# Slot_Pullups_and_Pulldowns.net
KiCad netlist of a schematic drawn in Altium Designer
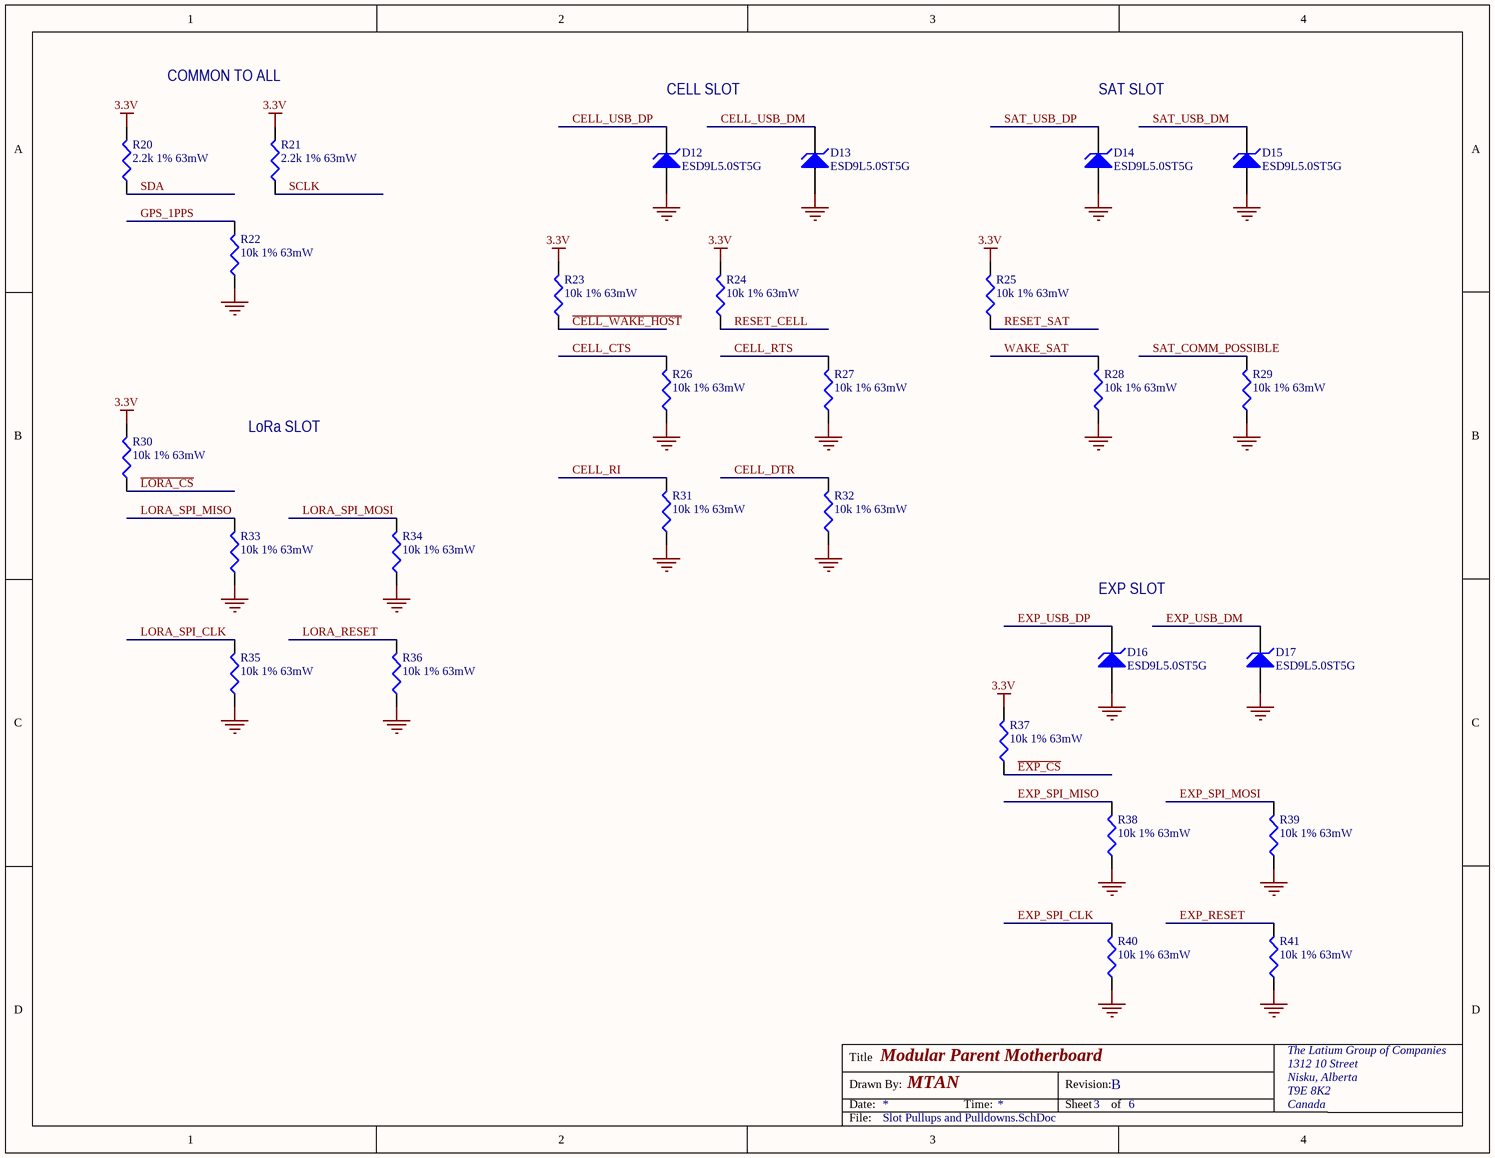
[diagram p0: Slot Pullups and Pulldowns.SchDoc]

(export (version "E")
  (design (tool "Eeschema 10.0.6"))
  (components
    (comp (ref "D12")
      (value "ESD9L5.0ST5G")
      (footprint "SOD-923")
      (description "TVS DIODE 5V 9.8V SOD923")
      (fields (field (name "MANUFACTURER") "ON Semiconductor"))
      (libsource (lib "Miscellaneous Devices") (part "D Zener"))
    )
    (comp (ref "D13")
      (value "ESD9L5.0ST5G")
      (footprint "SOD-923")
      (description "TVS DIODE 5V 9.8V SOD923")
      (fields (field (name "MANUFACTURER") "ON Semiconductor"))
      (libsource (lib "Miscellaneous Devices") (part "D Zener"))
    )
    (comp (ref "D14")
      (value "ESD9L5.0ST5G")
      (footprint "SOD-923")
      (description "TVS DIODE 5V 9.8V SOD923")
      (fields (field (name "MANUFACTURER") "ON Semiconductor"))
      (libsource (lib "Miscellaneous Devices") (part "D Zener"))
    )
    (comp (ref "D15")
      (value "ESD9L5.0ST5G")
      (footprint "SOD-923")
      (description "TVS DIODE 5V 9.8V SOD923")
      (fields (field (name "MANUFACTURER") "ON Semiconductor"))
      (libsource (lib "Miscellaneous Devices") (part "D Zener"))
    )
    (comp (ref "D16")
      (value "ESD9L5.0ST5G")
      (footprint "SOD-923")
      (description "TVS DIODE 5V 9.8V SOD923")
      (fields (field (name "MANUFACTURER") "ON Semiconductor"))
      (libsource (lib "Miscellaneous Devices") (part "D Zener"))
    )
    (comp (ref "D17")
      (value "ESD9L5.0ST5G")
      (footprint "SOD-923")
      (description "TVS DIODE 5V 9.8V SOD923")
      (fields (field (name "MANUFACTURER") "ON Semiconductor"))
      (libsource (lib "Miscellaneous Devices") (part "D Zener"))
    )
    (comp (ref "R20")
      (value "2.2k 1% 63mW")
      (footprint "RESC1005L")
      (description "Resistor")
      (libsource (lib "Miscellaneous Devices") (part "Res3"))
    )
    (comp (ref "R21")
      (value "2.2k 1% 63mW")
      (footprint "RESC1005L")
      (description "Resistor")
      (libsource (lib "Miscellaneous Devices") (part "Res3"))
    )
    (comp (ref "R22")
      (value "10k 1% 63mW")
      (footprint "RESC1005L")
      (description "Resistor")
      (libsource (lib "Miscellaneous Devices") (part "Res3"))
    )
    (comp (ref "R23")
      (value "10k 1% 63mW")
      (footprint "RESC1005L")
      (description "Resistor")
      (libsource (lib "Miscellaneous Devices") (part "Res3"))
    )
    (comp (ref "R24")
      (value "10k 1% 63mW")
      (footprint "RESC1005L")
      (description "Resistor")
      (libsource (lib "Miscellaneous Devices") (part "Res3"))
    )
    (comp (ref "R25")
      (value "10k 1% 63mW")
      (footprint "RESC1005L")
      (description "Resistor")
      (libsource (lib "Miscellaneous Devices") (part "Res3"))
    )
    (comp (ref "R26")
      (value "10k 1% 63mW")
      (footprint "RESC1005L")
      (description "Resistor")
      (libsource (lib "Miscellaneous Devices") (part "Res3"))
    )
    (comp (ref "R27")
      (value "10k 1% 63mW")
      (footprint "RESC1005L")
      (description "Resistor")
      (libsource (lib "Miscellaneous Devices") (part "Res3"))
    )
    (comp (ref "R28")
      (value "10k 1% 63mW")
      (footprint "RESC1005L")
      (description "Resistor")
      (libsource (lib "Miscellaneous Devices") (part "Res3"))
    )
    (comp (ref "R29")
      (value "10k 1% 63mW")
      (footprint "RESC1005L")
      (description "Resistor")
      (libsource (lib "Miscellaneous Devices") (part "Res3"))
    )
    (comp (ref "R30")
      (value "10k 1% 63mW")
      (footprint "RESC1005L")
      (description "Resistor")
      (libsource (lib "Miscellaneous Devices") (part "Res3"))
    )
    (comp (ref "R31")
      (value "10k 1% 63mW")
      (footprint "RESC1005L")
      (description "Resistor")
      (libsource (lib "Miscellaneous Devices") (part "Res3"))
    )
    (comp (ref "R32")
      (value "10k 1% 63mW")
      (footprint "RESC1005L")
      (description "Resistor")
      (libsource (lib "Miscellaneous Devices") (part "Res3"))
    )
    (comp (ref "R33")
      (value "10k 1% 63mW")
      (footprint "RESC1005L")
      (description "Resistor")
      (libsource (lib "Miscellaneous Devices") (part "Res3"))
    )
    (comp (ref "R34")
      (value "10k 1% 63mW")
      (footprint "RESC1005L")
      (description "Resistor")
      (libsource (lib "Miscellaneous Devices") (part "Res3"))
    )
    (comp (ref "R35")
      (value "10k 1% 63mW")
      (footprint "RESC1005L")
      (description "Resistor")
      (libsource (lib "Miscellaneous Devices") (part "Res3"))
    )
    (comp (ref "R36")
      (value "10k 1% 63mW")
      (footprint "RESC1005L")
      (description "Resistor")
      (libsource (lib "Miscellaneous Devices") (part "Res3"))
    )
    (comp (ref "R37")
      (value "10k 1% 63mW")
      (footprint "RESC1005L")
      (description "Resistor")
      (libsource (lib "Miscellaneous Devices") (part "Res3"))
    )
    (comp (ref "R38")
      (value "10k 1% 63mW")
      (footprint "RESC1005L")
      (description "Resistor")
      (libsource (lib "Miscellaneous Devices") (part "Res3"))
    )
    (comp (ref "R39")
      (value "10k 1% 63mW")
      (footprint "RESC1005L")
      (description "Resistor")
      (libsource (lib "Miscellaneous Devices") (part "Res3"))
    )
    (comp (ref "R40")
      (value "10k 1% 63mW")
      (footprint "RESC1005L")
      (description "Resistor")
      (libsource (lib "Miscellaneous Devices") (part "Res3"))
    )
    (comp (ref "R41")
      (value "10k 1% 63mW")
      (footprint "RESC1005L")
      (description "Resistor")
      (libsource (lib "Miscellaneous Devices") (part "Res3"))
    )
  )
  (nets
    (net (code "1") (name "/CELL_CTS") (class "Default")
      (node (ref "R26") (pin "2") (pinfunction "2_2") (pintype "passive"))
    )
    (net (code "2") (name "/CELL_DTR") (class "Default")
      (node (ref "R32") (pin "2") (pinfunction "2_2") (pintype "passive"))
    )
    (net (code "3") (name "/CELL_RI") (class "Default")
      (node (ref "R31") (pin "2") (pinfunction "2_2") (pintype "passive"))
    )
    (net (code "4") (name "/CELL_RTS") (class "Default")
      (node (ref "R27") (pin "2") (pinfunction "2_2") (pintype "passive"))
    )
    (net (code "5") (name "/CELL_USB_DM") (class "Default")
      (node (ref "D13") (pin "2") (pinfunction "K_2") (pintype "passive"))
    )
    (net (code "6") (name "/CELL_USB_DP") (class "Default")
      (node (ref "D12") (pin "2") (pinfunction "K_2") (pintype "passive"))
    )
    (net (code "7") (name "/EXP_RESET") (class "Default")
      (node (ref "R41") (pin "2") (pinfunction "2_2") (pintype "passive"))
    )
    (net (code "8") (name "/EXP_SPI_CLK") (class "Default")
      (node (ref "R40") (pin "2") (pinfunction "2_2") (pintype "passive"))
    )
    (net (code "9") (name "/EXP_SPI_MISO") (class "Default")
      (node (ref "R38") (pin "2") (pinfunction "2_2") (pintype "passive"))
    )
    (net (code "10") (name "/EXP_SPI_MOSI") (class "Default")
      (node (ref "R39") (pin "2") (pinfunction "2_2") (pintype "passive"))
    )
    (net (code "11") (name "/EXP_USB_DM") (class "Default")
      (node (ref "D17") (pin "2") (pinfunction "K_2") (pintype "passive"))
    )
    (net (code "12") (name "/EXP_USB_DP") (class "Default")
      (node (ref "D16") (pin "2") (pinfunction "K_2") (pintype "passive"))
    )
    (net (code "13") (name "/GPS_1PPS") (class "Default")
      (node (ref "R22") (pin "2") (pinfunction "2_2") (pintype "passive"))
    )
    (net (code "14") (name "/LORA_RESET") (class "Default")
      (node (ref "R36") (pin "2") (pinfunction "2_2") (pintype "passive"))
    )
    (net (code "15") (name "/LORA_SPI_CLK") (class "Default")
      (node (ref "R35") (pin "2") (pinfunction "2_2") (pintype "passive"))
    )
    (net (code "16") (name "/LORA_SPI_MISO") (class "Default")
      (node (ref "R33") (pin "2") (pinfunction "2_2") (pintype "passive"))
    )
    (net (code "17") (name "/LORA_SPI_MOSI") (class "Default")
      (node (ref "R34") (pin "2") (pinfunction "2_2") (pintype "passive"))
    )
    (net (code "18") (name "/RESET_CELL") (class "Default")
      (node (ref "R24") (pin "1") (pinfunction "1_1") (pintype "passive"))
    )
    (net (code "19") (name "/RESET_SAT") (class "Default")
      (node (ref "R25") (pin "1") (pinfunction "1_1") (pintype "passive"))
    )
    (net (code "20") (name "/SAT_COMM_POSSIBLE") (class "Default")
      (node (ref "R29") (pin "2") (pinfunction "2_2") (pintype "passive"))
    )
    (net (code "21") (name "/SAT_USB_DM") (class "Default")
      (node (ref "D15") (pin "2") (pinfunction "K_2") (pintype "passive"))
    )
    (net (code "22") (name "/SAT_USB_DP") (class "Default")
      (node (ref "D14") (pin "2") (pinfunction "K_2") (pintype "passive"))
    )
    (net (code "23") (name "/SCLK") (class "Default")
      (node (ref "R21") (pin "1") (pinfunction "1_1") (pintype "passive"))
    )
    (net (code "24") (name "/SDA") (class "Default")
      (node (ref "R20") (pin "1") (pinfunction "1_1") (pintype "passive"))
    )
    (net (code "25") (name "/WAKE_SAT") (class "Default")
      (node (ref "R28") (pin "2") (pinfunction "2_2") (pintype "passive"))
    )
    (net (code "26") (name "/~{CELL_WAKE_HOST}") (class "Default")
      (node (ref "R23") (pin "1") (pinfunction "1_1") (pintype "passive"))
    )
    (net (code "27") (name "/~{EXP_CS}") (class "Default")
      (node (ref "R37") (pin "1") (pinfunction "1_1") (pintype "passive"))
    )
    (net (code "28") (name "/~{LORA_CS}") (class "Default")
      (node (ref "R30") (pin "1") (pinfunction "1_1") (pintype "passive"))
    )
    (net (code "29") (name "3.3V") (class "Default")
      (node (ref "R20") (pin "2") (pinfunction "2_2") (pintype "passive"))
      (node (ref "R21") (pin "2") (pinfunction "2_2") (pintype "passive"))
      (node (ref "R23") (pin "2") (pinfunction "2_2") (pintype "passive"))
      (node (ref "R24") (pin "2") (pinfunction "2_2") (pintype "passive"))
      (node (ref "R25") (pin "2") (pinfunction "2_2") (pintype "passive"))
      (node (ref "R30") (pin "2") (pinfunction "2_2") (pintype "passive"))
      (node (ref "R37") (pin "2") (pinfunction "2_2") (pintype "passive"))
    )
    (net (code "30") (name "GND") (class "Default")
      (node (ref "D12") (pin "1") (pinfunction "A_1") (pintype "passive"))
      (node (ref "D13") (pin "1") (pinfunction "A_1") (pintype "passive"))
      (node (ref "D14") (pin "1") (pinfunction "A_1") (pintype "passive"))
      (node (ref "D15") (pin "1") (pinfunction "A_1") (pintype "passive"))
      (node (ref "D16") (pin "1") (pinfunction "A_1") (pintype "passive"))
      (node (ref "D17") (pin "1") (pinfunction "A_1") (pintype "passive"))
      (node (ref "R22") (pin "1") (pinfunction "1_1") (pintype "passive"))
      (node (ref "R26") (pin "1") (pinfunction "1_1") (pintype "passive"))
      (node (ref "R27") (pin "1") (pinfunction "1_1") (pintype "passive"))
      (node (ref "R28") (pin "1") (pinfunction "1_1") (pintype "passive"))
      (node (ref "R29") (pin "1") (pinfunction "1_1") (pintype "passive"))
      (node (ref "R31") (pin "1") (pinfunction "1_1") (pintype "passive"))
      (node (ref "R32") (pin "1") (pinfunction "1_1") (pintype "passive"))
      (node (ref "R33") (pin "1") (pinfunction "1_1") (pintype "passive"))
      (node (ref "R34") (pin "1") (pinfunction "1_1") (pintype "passive"))
      (node (ref "R35") (pin "1") (pinfunction "1_1") (pintype "passive"))
      (node (ref "R36") (pin "1") (pinfunction "1_1") (pintype "passive"))
      (node (ref "R38") (pin "1") (pinfunction "1_1") (pintype "passive"))
      (node (ref "R39") (pin "1") (pinfunction "1_1") (pintype "passive"))
      (node (ref "R40") (pin "1") (pinfunction "1_1") (pintype "passive"))
      (node (ref "R41") (pin "1") (pinfunction "1_1") (pintype "passive"))
    )
  )
)
